# ProPrj_LED__2025-12-14-09-43-45.net
KiCad netlist of a schematic drawn in EasyEDA Pro
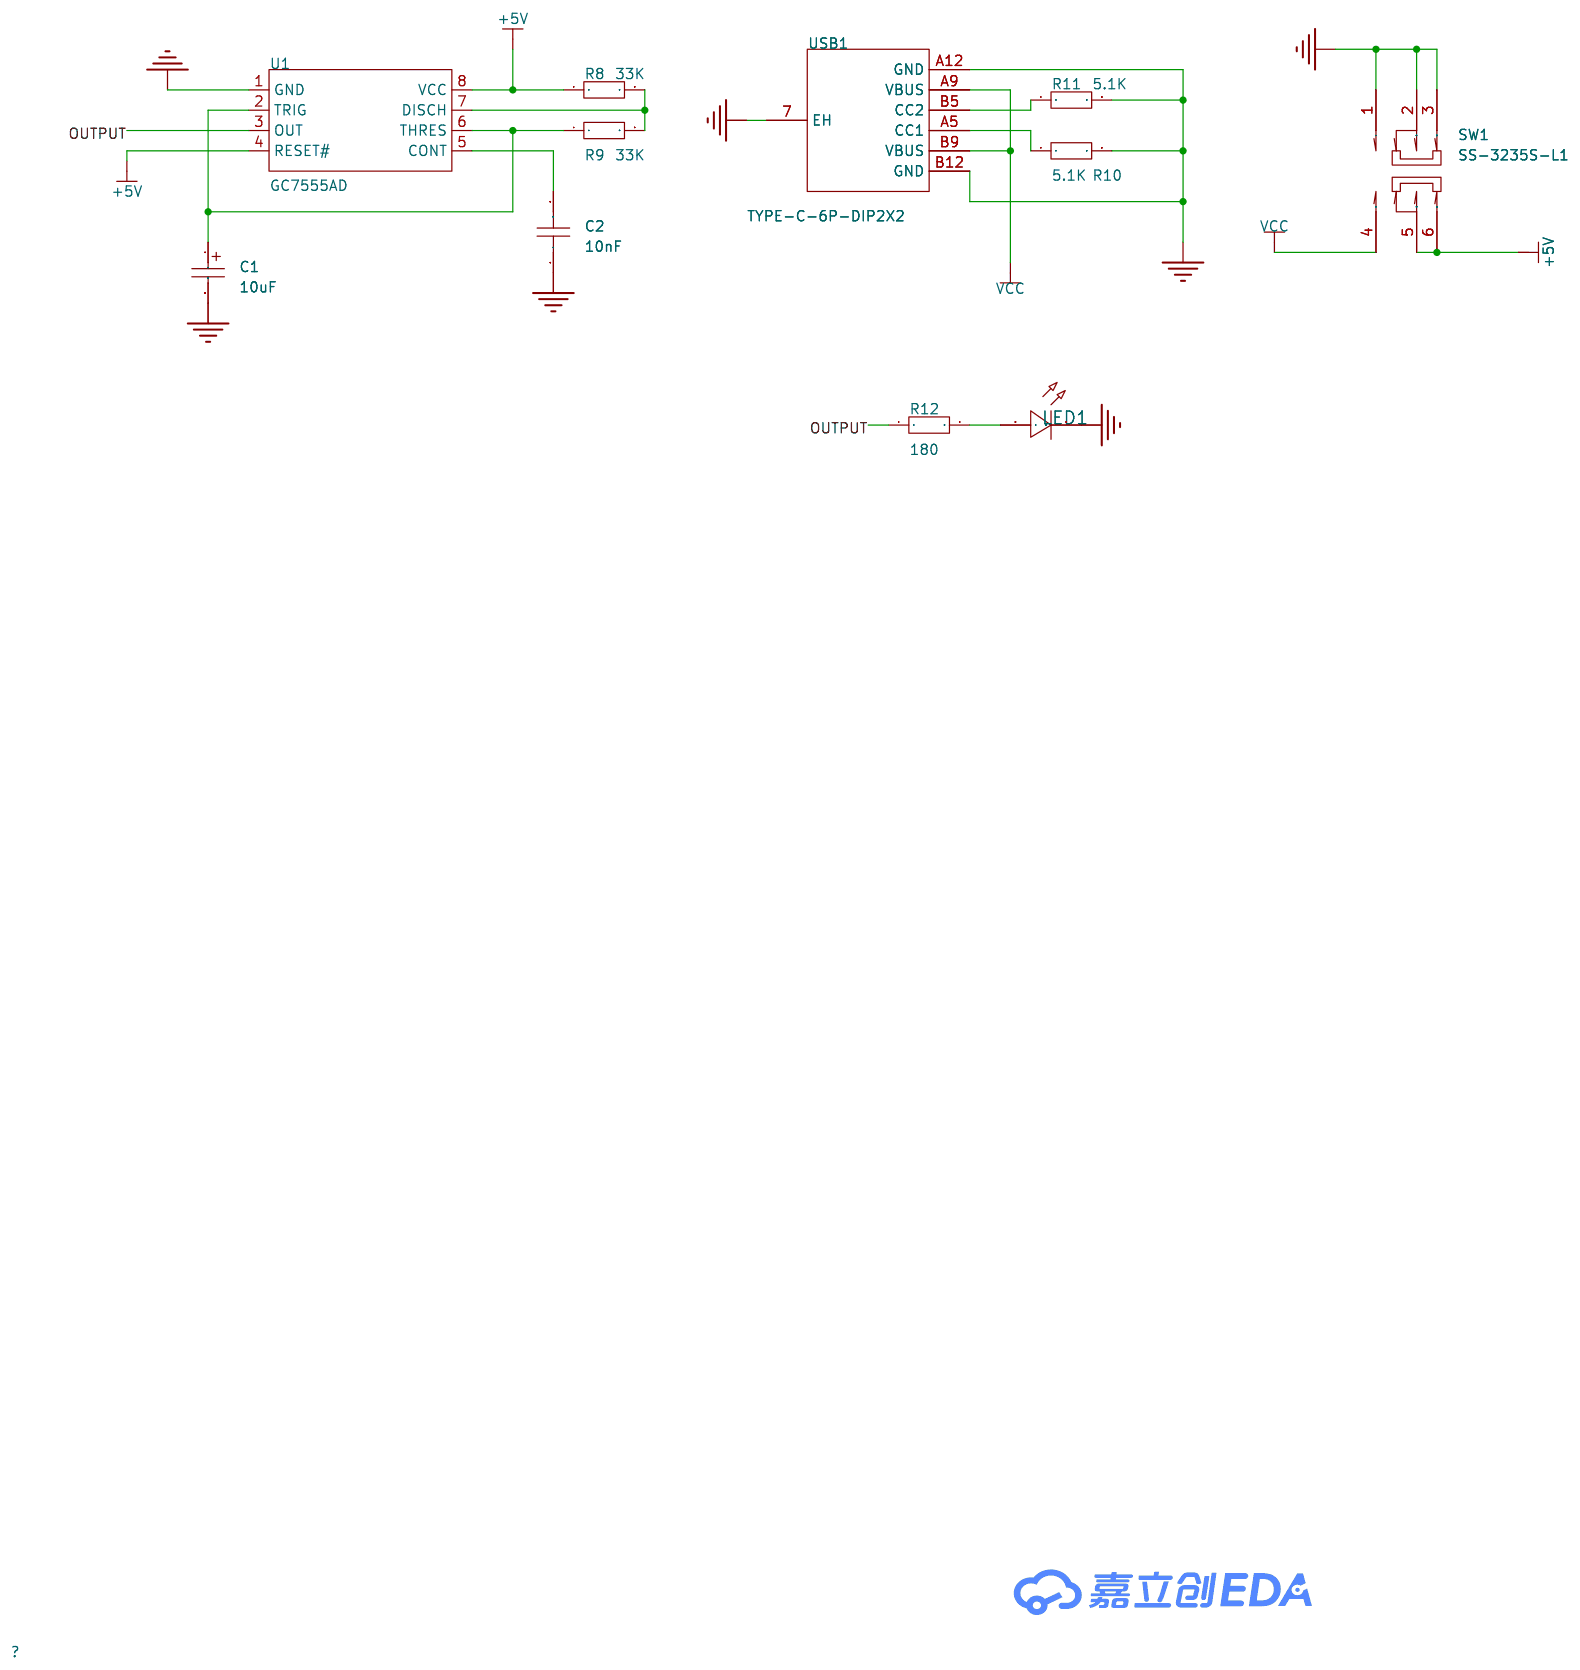
[diagram p0: schematic sheet]

(export (version "E")
  (design (tool "Eeschema 10.0.6"))
  (components
    (comp (ref "C1")
      (value "10uF")
      (footprint "easyedapro:C_Ele_SMD_3x5.4mm")
      (libsource (lib "easyedapro") (part "CAP"))
    )
    (comp (ref "C2")
      (value "10nF")
      (footprint "easyedapro:C0603")
      (libsource (lib "easyedapro") (part "Capacitance"))
    )
    (comp (ref "LED1")
      (value "~")
      (footprint "easyedapro:LED_0603")
      (libsource (lib "easyedapro") (part "LED_R"))
    )
    (comp (ref "R8") (value "33K") (footprint "easyedapro:R0805") (libsource (lib "easyedapro") (part "电阻")))
    (comp (ref "R9") (value "33K") (footprint "easyedapro:R0805") (libsource (lib "easyedapro") (part "电阻")))
    (comp (ref "R10")
      (value "5.1K")
      (footprint "easyedapro:R0805")
      (libsource (lib "easyedapro") (part "电阻"))
    )
    (comp (ref "R11")
      (value "5.1K")
      (footprint "easyedapro:R0805")
      (libsource (lib "easyedapro") (part "电阻"))
    )
    (comp (ref "R12") (value "180") (footprint "easyedapro:R0805") (libsource (lib "easyedapro") (part "电阻")))
    (comp (ref "SW1")
      (value "SS-3235S-L1")
      (footprint "easyedapro:SW-SMD_SS-3235S-LX")
      (description "电路结构:双刀双掷;安装方式:卧贴;开关颜色:黑色;额定电流:50mA;额定电压:12V;工作寿命:1万次;")
      (fields (field (name "Manufacturer") "XKB Connection(中国星坤)"))
      (libsource (lib "easyedapro") (part "SS-3235S-L1"))
    )
    (comp (ref "U1")
      (value "GC7555AD")
      (footprint "easyedapro:PDIP-8_L9.5-W6.4-P2.54-LS7.6-BL")
      (description "通用计时器：时基电路；计时；脉冲产生；满足用户（至少工业级）自主可控的需求。")
      (fields (field (name "Manufacturer") "Sungine(双竞集成)"))
      (libsource (lib "easyedapro") (part "GC7555AD"))
    )
    (comp (ref "USB1")
      (value "TYPE-C-6P-DIP2X2")
      (footprint "easyedapro:TYPE-C-SMD_TYPE-C-6P")
      (libsource (lib "easyedapro") (part "TYPE-C-6P-DIP2X2"))
    )
  )
  (nets
    (net (code "1") (name "+5V") (class "Default")
      (node (ref "R8") (pin "1") (pinfunction "1_1") (pintype "input"))
      (node (ref "SW1") (pin "5") (pinfunction "5_5") (pintype "unspecified"))
      (node (ref "SW1") (pin "6") (pinfunction "6_6") (pintype "unspecified"))
      (node (ref "U1") (pin "4") (pinfunction "RESET#_4") (pintype "unspecified"))
      (node (ref "U1") (pin "8") (pinfunction "VCC_8") (pintype "unspecified"))
    )
    (net (code "2") (name "/OUTPUT") (class "Default")
      (node (ref "R12") (pin "1") (pinfunction "1_1") (pintype "input"))
      (node (ref "U1") (pin "3") (pinfunction "OUT_3") (pintype "unspecified"))
    )
    (net (code "3") (name "GND") (class "Default")
      (node (ref "C1") (pin "2") (pinfunction "2_2") (pintype "input"))
      (node (ref "C2") (pin "1") (pinfunction "1_1") (pintype "input"))
      (node (ref "LED1") (pin "1") (pinfunction "C_1") (pintype "input"))
      (node (ref "R10") (pin "2") (pinfunction "2_2") (pintype "input"))
      (node (ref "R11") (pin "2") (pinfunction "2_2") (pintype "input"))
      (node (ref "SW1") (pin "1") (pinfunction "1_1") (pintype "unspecified"))
      (node (ref "SW1") (pin "2") (pinfunction "2_2") (pintype "unspecified"))
      (node (ref "SW1") (pin "3") (pinfunction "3_3") (pintype "unspecified"))
      (node (ref "U1") (pin "1") (pinfunction "GND_1") (pintype "unspecified"))
      (node (ref "USB1") (pin "7") (pinfunction "EH_7") (pintype "unspecified"))
      (node (ref "USB1") (pin "A12") (pinfunction "GND_A12") (pintype "unspecified"))
      (node (ref "USB1") (pin "B12") (pinfunction "GND_B12") (pintype "unspecified"))
    )
    (net (code "4") (name "Net-(LED1-A)") (class "Default")
      (node (ref "LED1") (pin "2") (pinfunction "A_2") (pintype "input"))
      (node (ref "R12") (pin "2") (pinfunction "2_2") (pintype "input"))
    )
    (net (code "5") (name "Net-(U1-CONT)") (class "Default")
      (node (ref "C2") (pin "2") (pinfunction "2_2") (pintype "input"))
      (node (ref "U1") (pin "5") (pinfunction "CONT_5") (pintype "unspecified"))
    )
    (net (code "6") (name "Net-(U1-DISCH)") (class "Default")
      (node (ref "R8") (pin "2") (pinfunction "2_2") (pintype "input"))
      (node (ref "R9") (pin "2") (pinfunction "2_2") (pintype "input"))
      (node (ref "U1") (pin "7") (pinfunction "DISCH_7") (pintype "unspecified"))
    )
    (net (code "7") (name "Net-(U1-THRES)") (class "Default")
      (node (ref "C1") (pin "1") (pinfunction "1_1") (pintype "input"))
      (node (ref "R9") (pin "1") (pinfunction "1_1") (pintype "input"))
      (node (ref "U1") (pin "2") (pinfunction "TRIG_2") (pintype "unspecified"))
      (node (ref "U1") (pin "6") (pinfunction "THRES_6") (pintype "unspecified"))
    )
    (net (code "8") (name "Net-(USB1-CC1)") (class "Default")
      (node (ref "R10") (pin "1") (pinfunction "1_1") (pintype "input"))
      (node (ref "USB1") (pin "A5") (pinfunction "CC1_A5") (pintype "unspecified"))
    )
    (net (code "9") (name "Net-(USB1-CC2)") (class "Default")
      (node (ref "R11") (pin "1") (pinfunction "1_1") (pintype "input"))
      (node (ref "USB1") (pin "B5") (pinfunction "CC2_B5") (pintype "unspecified"))
    )
    (net (code "10") (name "VCC") (class "Default")
      (node (ref "SW1") (pin "4") (pinfunction "4_4") (pintype "unspecified"))
      (node (ref "USB1") (pin "A9") (pinfunction "VBUS_A9") (pintype "unspecified"))
      (node (ref "USB1") (pin "B9") (pinfunction "VBUS_B9") (pintype "unspecified"))
    )
  )
)
